# v2164_quad_VCA.net
KiCad netlist of a schematic drawn in EAGLE
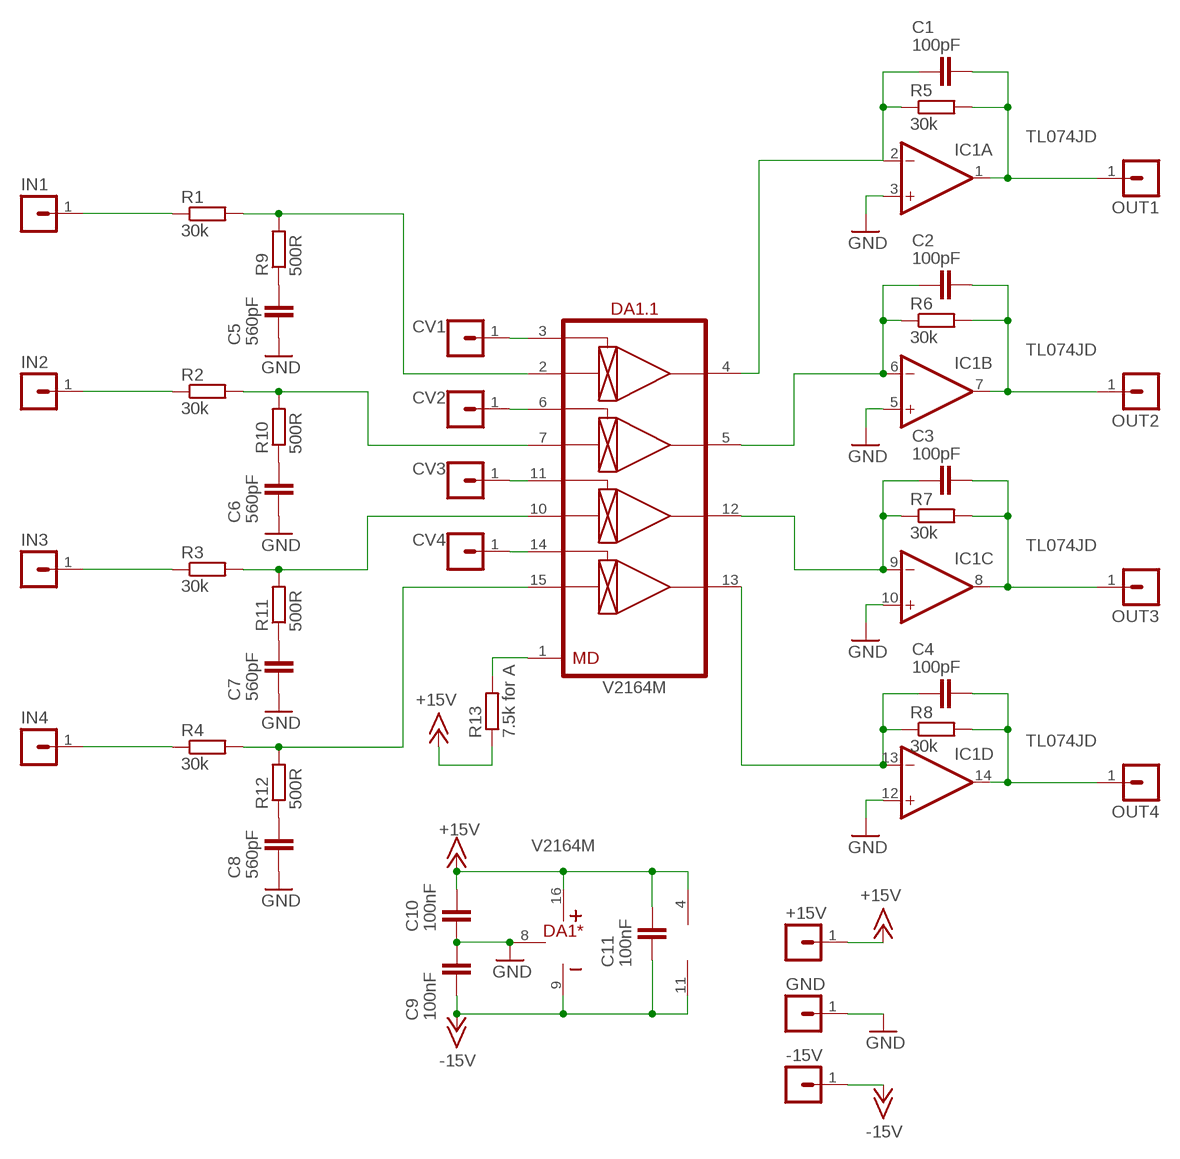
[diagram p0: schematic, sheet 1]

(export (version "E")
  (design (tool "Eeschema 10.0.6"))
  (components
    (comp (ref "+15V")
      (value "MA01-1JN")
      (footprint "eagle-import:MA01N-1J")
      (libsource (lib "eagle-import") (part "MA01-1JN"))
    )
    (comp (ref "-15V")
      (value "MA01-1JN")
      (footprint "eagle-import:MA01N-1J")
      (libsource (lib "eagle-import") (part "MA01-1JN"))
    )
    (comp (ref "C1")
      (value "100pF")
      (footprint "eagle-import:C0603")
      (libsource (lib "eagle-import") (part "C-EUC0603"))
    )
    (comp (ref "C2")
      (value "100pF")
      (footprint "eagle-import:C0603")
      (libsource (lib "eagle-import") (part "C-EUC0603"))
    )
    (comp (ref "C3")
      (value "100pF")
      (footprint "eagle-import:C0603")
      (libsource (lib "eagle-import") (part "C-EUC0603"))
    )
    (comp (ref "C4")
      (value "100pF")
      (footprint "eagle-import:C0603")
      (libsource (lib "eagle-import") (part "C-EUC0603"))
    )
    (comp (ref "C5")
      (value "560pF")
      (footprint "eagle-import:C0603")
      (libsource (lib "eagle-import") (part "C-EUC0603"))
    )
    (comp (ref "C6")
      (value "560pF")
      (footprint "eagle-import:C0603")
      (libsource (lib "eagle-import") (part "C-EUC0603"))
    )
    (comp (ref "C7")
      (value "560pF")
      (footprint "eagle-import:C0603")
      (libsource (lib "eagle-import") (part "C-EUC0603"))
    )
    (comp (ref "C8")
      (value "560pF")
      (footprint "eagle-import:C0603")
      (libsource (lib "eagle-import") (part "C-EUC0603"))
    )
    (comp (ref "C9")
      (value "100nF")
      (footprint "eagle-import:C0603")
      (libsource (lib "eagle-import") (part "C-EUC0603"))
    )
    (comp (ref "C10")
      (value "100nF")
      (footprint "eagle-import:C0603")
      (libsource (lib "eagle-import") (part "C-EUC0603"))
    )
    (comp (ref "C11")
      (value "100nF")
      (footprint "eagle-import:C0603")
      (libsource (lib "eagle-import") (part "C-EUC0603"))
    )
    (comp (ref "CV1")
      (value "MA01-1JN")
      (footprint "eagle-import:MA01N-1J")
      (libsource (lib "eagle-import") (part "MA01-1JN"))
    )
    (comp (ref "CV2")
      (value "MA01-1JN")
      (footprint "eagle-import:MA01N-1J")
      (libsource (lib "eagle-import") (part "MA01-1JN"))
    )
    (comp (ref "CV3")
      (value "MA01-1JN")
      (footprint "eagle-import:MA01N-1J")
      (libsource (lib "eagle-import") (part "MA01-1JN"))
    )
    (comp (ref "CV4")
      (value "MA01-1JN")
      (footprint "eagle-import:MA01N-1J")
      (libsource (lib "eagle-import") (part "MA01-1JN"))
    )
    (comp (ref "DA1")
      (value "V2164M")
      (footprint "eagle-import:SO-16")
      (libsource (lib "eagle-import") (part "V2164M"))
    )
    (comp (ref "GND")
      (value "MA01-1JN")
      (footprint "eagle-import:MA01N-1J")
      (libsource (lib "eagle-import") (part "MA01-1JN"))
    )
    (comp (ref "IC1")
      (value "TL074JD")
      (footprint "eagle-import:SO14J")
      (libsource (lib "eagle-import") (part "TL074JD"))
    )
    (comp (ref "IN1")
      (value "MA01-1JN")
      (footprint "eagle-import:MA01N-1J")
      (libsource (lib "eagle-import") (part "MA01-1JN"))
    )
    (comp (ref "IN2")
      (value "MA01-1JN")
      (footprint "eagle-import:MA01N-1J")
      (libsource (lib "eagle-import") (part "MA01-1JN"))
    )
    (comp (ref "IN3")
      (value "MA01-1JN")
      (footprint "eagle-import:MA01N-1J")
      (libsource (lib "eagle-import") (part "MA01-1JN"))
    )
    (comp (ref "IN4")
      (value "MA01-1JN")
      (footprint "eagle-import:MA01N-1J")
      (libsource (lib "eagle-import") (part "MA01-1JN"))
    )
    (comp (ref "OUT1")
      (value "MA01-1JN")
      (footprint "eagle-import:MA01N-1J")
      (libsource (lib "eagle-import") (part "MA01-1JN"))
    )
    (comp (ref "OUT2")
      (value "MA01-1JN")
      (footprint "eagle-import:MA01N-1J")
      (libsource (lib "eagle-import") (part "MA01-1JN"))
    )
    (comp (ref "OUT3")
      (value "MA01-1JN")
      (footprint "eagle-import:MA01N-1J")
      (libsource (lib "eagle-import") (part "MA01-1JN"))
    )
    (comp (ref "OUT4")
      (value "MA01-1JN")
      (footprint "eagle-import:MA01N-1J")
      (libsource (lib "eagle-import") (part "MA01-1JN"))
    )
    (comp (ref "R1")
      (value "30k")
      (footprint "eagle-import:R0603")
      (libsource (lib "eagle-import") (part "R-EU_R0603"))
    )
    (comp (ref "R2")
      (value "30k")
      (footprint "eagle-import:R0603")
      (libsource (lib "eagle-import") (part "R-EU_R0603"))
    )
    (comp (ref "R3")
      (value "30k")
      (footprint "eagle-import:R0603")
      (libsource (lib "eagle-import") (part "R-EU_R0603"))
    )
    (comp (ref "R4")
      (value "30k")
      (footprint "eagle-import:R0603")
      (libsource (lib "eagle-import") (part "R-EU_R0603"))
    )
    (comp (ref "R5")
      (value "30k")
      (footprint "eagle-import:R0603")
      (libsource (lib "eagle-import") (part "R-EU_R0603"))
    )
    (comp (ref "R6")
      (value "30k")
      (footprint "eagle-import:R0603")
      (libsource (lib "eagle-import") (part "R-EU_R0603"))
    )
    (comp (ref "R7")
      (value "30k")
      (footprint "eagle-import:R0603")
      (libsource (lib "eagle-import") (part "R-EU_R0603"))
    )
    (comp (ref "R8")
      (value "30k")
      (footprint "eagle-import:R0603")
      (libsource (lib "eagle-import") (part "R-EU_R0603"))
    )
    (comp (ref "R9")
      (value "500R")
      (footprint "eagle-import:R0603")
      (libsource (lib "eagle-import") (part "R-EU_R0603"))
    )
    (comp (ref "R10")
      (value "500R")
      (footprint "eagle-import:R0603")
      (libsource (lib "eagle-import") (part "R-EU_R0603"))
    )
    (comp (ref "R11")
      (value "500R")
      (footprint "eagle-import:R0603")
      (libsource (lib "eagle-import") (part "R-EU_R0603"))
    )
    (comp (ref "R12")
      (value "500R")
      (footprint "eagle-import:R0603")
      (libsource (lib "eagle-import") (part "R-EU_R0603"))
    )
    (comp (ref "R13")
      (value "7.5k for A")
      (footprint "eagle-import:R0603")
      (libsource (lib "eagle-import") (part "R-EU_R0603"))
    )
  )
  (nets
    (net (code "1") (name "+15V") (class "Default")
      (node (ref "+15V") (pin "1") (pinfunction "1_1") (pintype "passive"))
      (node (ref "C10") (pin "2") (pinfunction "2_2") (pintype "passive"))
      (node (ref "C11") (pin "2") (pinfunction "2_2") (pintype "passive"))
      (node (ref "DA1") (pin "16") (pinfunction "V+_16") (pintype "power_in"))
      (node (ref "IC1") (pin "4") (pinfunction "V+_4") (pintype "power_in"))
      (node (ref "R13") (pin "1") (pinfunction "1_1") (pintype "passive"))
    )
    (net (code "2") (name "-15V") (class "Default")
      (node (ref "-15V") (pin "1") (pinfunction "1_1") (pintype "passive"))
      (node (ref "C11") (pin "1") (pinfunction "1_1") (pintype "passive"))
      (node (ref "C9") (pin "1") (pinfunction "1_1") (pintype "passive"))
      (node (ref "DA1") (pin "9") (pinfunction "V-_9") (pintype "power_in"))
      (node (ref "IC1") (pin "11") (pinfunction "V-_11") (pintype "power_in"))
    )
    (net (code "3") (name "GND") (class "Default")
      (node (ref "C10") (pin "1") (pinfunction "1_1") (pintype "passive"))
      (node (ref "C5") (pin "1") (pinfunction "1_1") (pintype "passive"))
      (node (ref "C6") (pin "1") (pinfunction "1_1") (pintype "passive"))
      (node (ref "C7") (pin "1") (pinfunction "1_1") (pintype "passive"))
      (node (ref "C8") (pin "1") (pinfunction "1_1") (pintype "passive"))
      (node (ref "C9") (pin "2") (pinfunction "2_2") (pintype "passive"))
      (node (ref "DA1") (pin "8") (pinfunction "GND_8") (pintype "power_in"))
      (node (ref "GND") (pin "1") (pinfunction "1_1") (pintype "passive"))
      (node (ref "IC1") (pin "10") (pinfunction "+IN_10") (pintype "input"))
      (node (ref "IC1") (pin "12") (pinfunction "+IN_12") (pintype "input"))
      (node (ref "IC1") (pin "3") (pinfunction "+IN_3") (pintype "input"))
      (node (ref "IC1") (pin "5") (pinfunction "+IN_5") (pintype "input"))
    )
    (net (code "4") (name "Net-(C5-Pad2)") (class "Default")
      (node (ref "C5") (pin "2") (pinfunction "2_2") (pintype "passive"))
      (node (ref "R9") (pin "1") (pinfunction "1_1") (pintype "passive"))
    )
    (net (code "5") (name "Net-(C6-Pad2)") (class "Default")
      (node (ref "C6") (pin "2") (pinfunction "2_2") (pintype "passive"))
      (node (ref "R10") (pin "1") (pinfunction "1_1") (pintype "passive"))
    )
    (net (code "6") (name "Net-(C7-Pad2)") (class "Default")
      (node (ref "C7") (pin "2") (pinfunction "2_2") (pintype "passive"))
      (node (ref "R11") (pin "1") (pinfunction "1_1") (pintype "passive"))
    )
    (net (code "7") (name "Net-(C8-Pad2)") (class "Default")
      (node (ref "C8") (pin "2") (pinfunction "2_2") (pintype "passive"))
      (node (ref "R12") (pin "1") (pinfunction "1_1") (pintype "passive"))
    )
    (net (code "8") (name "Net-(DA1B-CV1)") (class "Default")
      (node (ref "CV1") (pin "1") (pinfunction "1_1") (pintype "passive"))
      (node (ref "DA1") (pin "3") (pinfunction "CV1_3") (pintype "input"))
    )
    (net (code "9") (name "Net-(DA1B-CV2)") (class "Default")
      (node (ref "CV2") (pin "1") (pinfunction "1_1") (pintype "passive"))
      (node (ref "DA1") (pin "6") (pinfunction "CV2_6") (pintype "input"))
    )
    (net (code "10") (name "Net-(DA1B-CV3)") (class "Default")
      (node (ref "CV3") (pin "1") (pinfunction "1_1") (pintype "passive"))
      (node (ref "DA1") (pin "11") (pinfunction "CV3_11") (pintype "input"))
    )
    (net (code "11") (name "Net-(DA1B-CV4)") (class "Default")
      (node (ref "CV4") (pin "1") (pinfunction "1_1") (pintype "passive"))
      (node (ref "DA1") (pin "14") (pinfunction "CV4_14") (pintype "input"))
    )
    (net (code "12") (name "Net-(DA1B-IN1)") (class "Default")
      (node (ref "DA1") (pin "2") (pinfunction "IN1_2") (pintype "input"))
      (node (ref "R1") (pin "2") (pinfunction "2_2") (pintype "passive"))
      (node (ref "R9") (pin "2") (pinfunction "2_2") (pintype "passive"))
    )
    (net (code "13") (name "Net-(DA1B-IN2)") (class "Default")
      (node (ref "DA1") (pin "7") (pinfunction "IN2_7") (pintype "input"))
      (node (ref "R10") (pin "2") (pinfunction "2_2") (pintype "passive"))
      (node (ref "R2") (pin "2") (pinfunction "2_2") (pintype "passive"))
    )
    (net (code "14") (name "Net-(DA1B-IN3)") (class "Default")
      (node (ref "DA1") (pin "10") (pinfunction "IN3_10") (pintype "input"))
      (node (ref "R11") (pin "2") (pinfunction "2_2") (pintype "passive"))
      (node (ref "R3") (pin "2") (pinfunction "2_2") (pintype "passive"))
    )
    (net (code "15") (name "Net-(DA1B-IN4)") (class "Default")
      (node (ref "DA1") (pin "15") (pinfunction "IN4_15") (pintype "input"))
      (node (ref "R12") (pin "2") (pinfunction "2_2") (pintype "passive"))
      (node (ref "R4") (pin "2") (pinfunction "2_2") (pintype "passive"))
    )
    (net (code "16") (name "Net-(DA1B-MD)") (class "Default")
      (node (ref "DA1") (pin "1") (pinfunction "MD_1") (pintype "output"))
      (node (ref "R13") (pin "2") (pinfunction "2_2") (pintype "passive"))
    )
    (net (code "17") (name "Net-(DA1B-OUT1)") (class "Default")
      (node (ref "C1") (pin "1") (pinfunction "1_1") (pintype "passive"))
      (node (ref "DA1") (pin "4") (pinfunction "OUT1_4") (pintype "output"))
      (node (ref "IC1") (pin "2") (pinfunction "-IN_2") (pintype "input"))
      (node (ref "R5") (pin "1") (pinfunction "1_1") (pintype "passive"))
    )
    (net (code "18") (name "Net-(DA1B-OUT2)") (class "Default")
      (node (ref "C2") (pin "1") (pinfunction "1_1") (pintype "passive"))
      (node (ref "DA1") (pin "5") (pinfunction "OUT2_5") (pintype "output"))
      (node (ref "IC1") (pin "6") (pinfunction "-IN_6") (pintype "input"))
      (node (ref "R6") (pin "1") (pinfunction "1_1") (pintype "passive"))
    )
    (net (code "19") (name "Net-(DA1B-OUT3)") (class "Default")
      (node (ref "C3") (pin "1") (pinfunction "1_1") (pintype "passive"))
      (node (ref "DA1") (pin "12") (pinfunction "OUT3_12") (pintype "output"))
      (node (ref "IC1") (pin "9") (pinfunction "-IN_9") (pintype "input"))
      (node (ref "R7") (pin "1") (pinfunction "1_1") (pintype "passive"))
    )
    (net (code "20") (name "Net-(DA1B-OUT4)") (class "Default")
      (node (ref "C4") (pin "1") (pinfunction "1_1") (pintype "passive"))
      (node (ref "DA1") (pin "13") (pinfunction "OUT4_13") (pintype "output"))
      (node (ref "IC1") (pin "13") (pinfunction "-IN_13") (pintype "input"))
      (node (ref "R8") (pin "1") (pinfunction "1_1") (pintype "passive"))
    )
    (net (code "21") (name "Net-(IC1A-OUT)") (class "Default")
      (node (ref "C1") (pin "2") (pinfunction "2_2") (pintype "passive"))
      (node (ref "IC1") (pin "1") (pinfunction "OUT_1") (pintype "output"))
      (node (ref "OUT1") (pin "1") (pinfunction "1_1") (pintype "passive"))
      (node (ref "R5") (pin "2") (pinfunction "2_2") (pintype "passive"))
    )
    (net (code "22") (name "Net-(IC1B-OUT)") (class "Default")
      (node (ref "C2") (pin "2") (pinfunction "2_2") (pintype "passive"))
      (node (ref "IC1") (pin "7") (pinfunction "OUT_7") (pintype "output"))
      (node (ref "OUT2") (pin "1") (pinfunction "1_1") (pintype "passive"))
      (node (ref "R6") (pin "2") (pinfunction "2_2") (pintype "passive"))
    )
    (net (code "23") (name "Net-(IC1C-OUT)") (class "Default")
      (node (ref "C3") (pin "2") (pinfunction "2_2") (pintype "passive"))
      (node (ref "IC1") (pin "8") (pinfunction "OUT_8") (pintype "output"))
      (node (ref "OUT3") (pin "1") (pinfunction "1_1") (pintype "passive"))
      (node (ref "R7") (pin "2") (pinfunction "2_2") (pintype "passive"))
    )
    (net (code "24") (name "Net-(IC1D-OUT)") (class "Default")
      (node (ref "C4") (pin "2") (pinfunction "2_2") (pintype "passive"))
      (node (ref "IC1") (pin "14") (pinfunction "OUT_14") (pintype "output"))
      (node (ref "OUT4") (pin "1") (pinfunction "1_1") (pintype "passive"))
      (node (ref "R8") (pin "2") (pinfunction "2_2") (pintype "passive"))
    )
    (net (code "25") (name "Net-(IN1-Pad1)") (class "Default")
      (node (ref "IN1") (pin "1") (pinfunction "1_1") (pintype "passive"))
      (node (ref "R1") (pin "1") (pinfunction "1_1") (pintype "passive"))
    )
    (net (code "26") (name "Net-(IN2-Pad1)") (class "Default")
      (node (ref "IN2") (pin "1") (pinfunction "1_1") (pintype "passive"))
      (node (ref "R2") (pin "1") (pinfunction "1_1") (pintype "passive"))
    )
    (net (code "27") (name "Net-(IN3-Pad1)") (class "Default")
      (node (ref "IN3") (pin "1") (pinfunction "1_1") (pintype "passive"))
      (node (ref "R3") (pin "1") (pinfunction "1_1") (pintype "passive"))
    )
    (net (code "28") (name "Net-(IN4-Pad1)") (class "Default")
      (node (ref "IN4") (pin "1") (pinfunction "1_1") (pintype "passive"))
      (node (ref "R4") (pin "1") (pinfunction "1_1") (pintype "passive"))
    )
  )
)
